# GRUBswitch_CustomHW_RevC.net
KiCad netlist of a schematic drawn in EAGLE
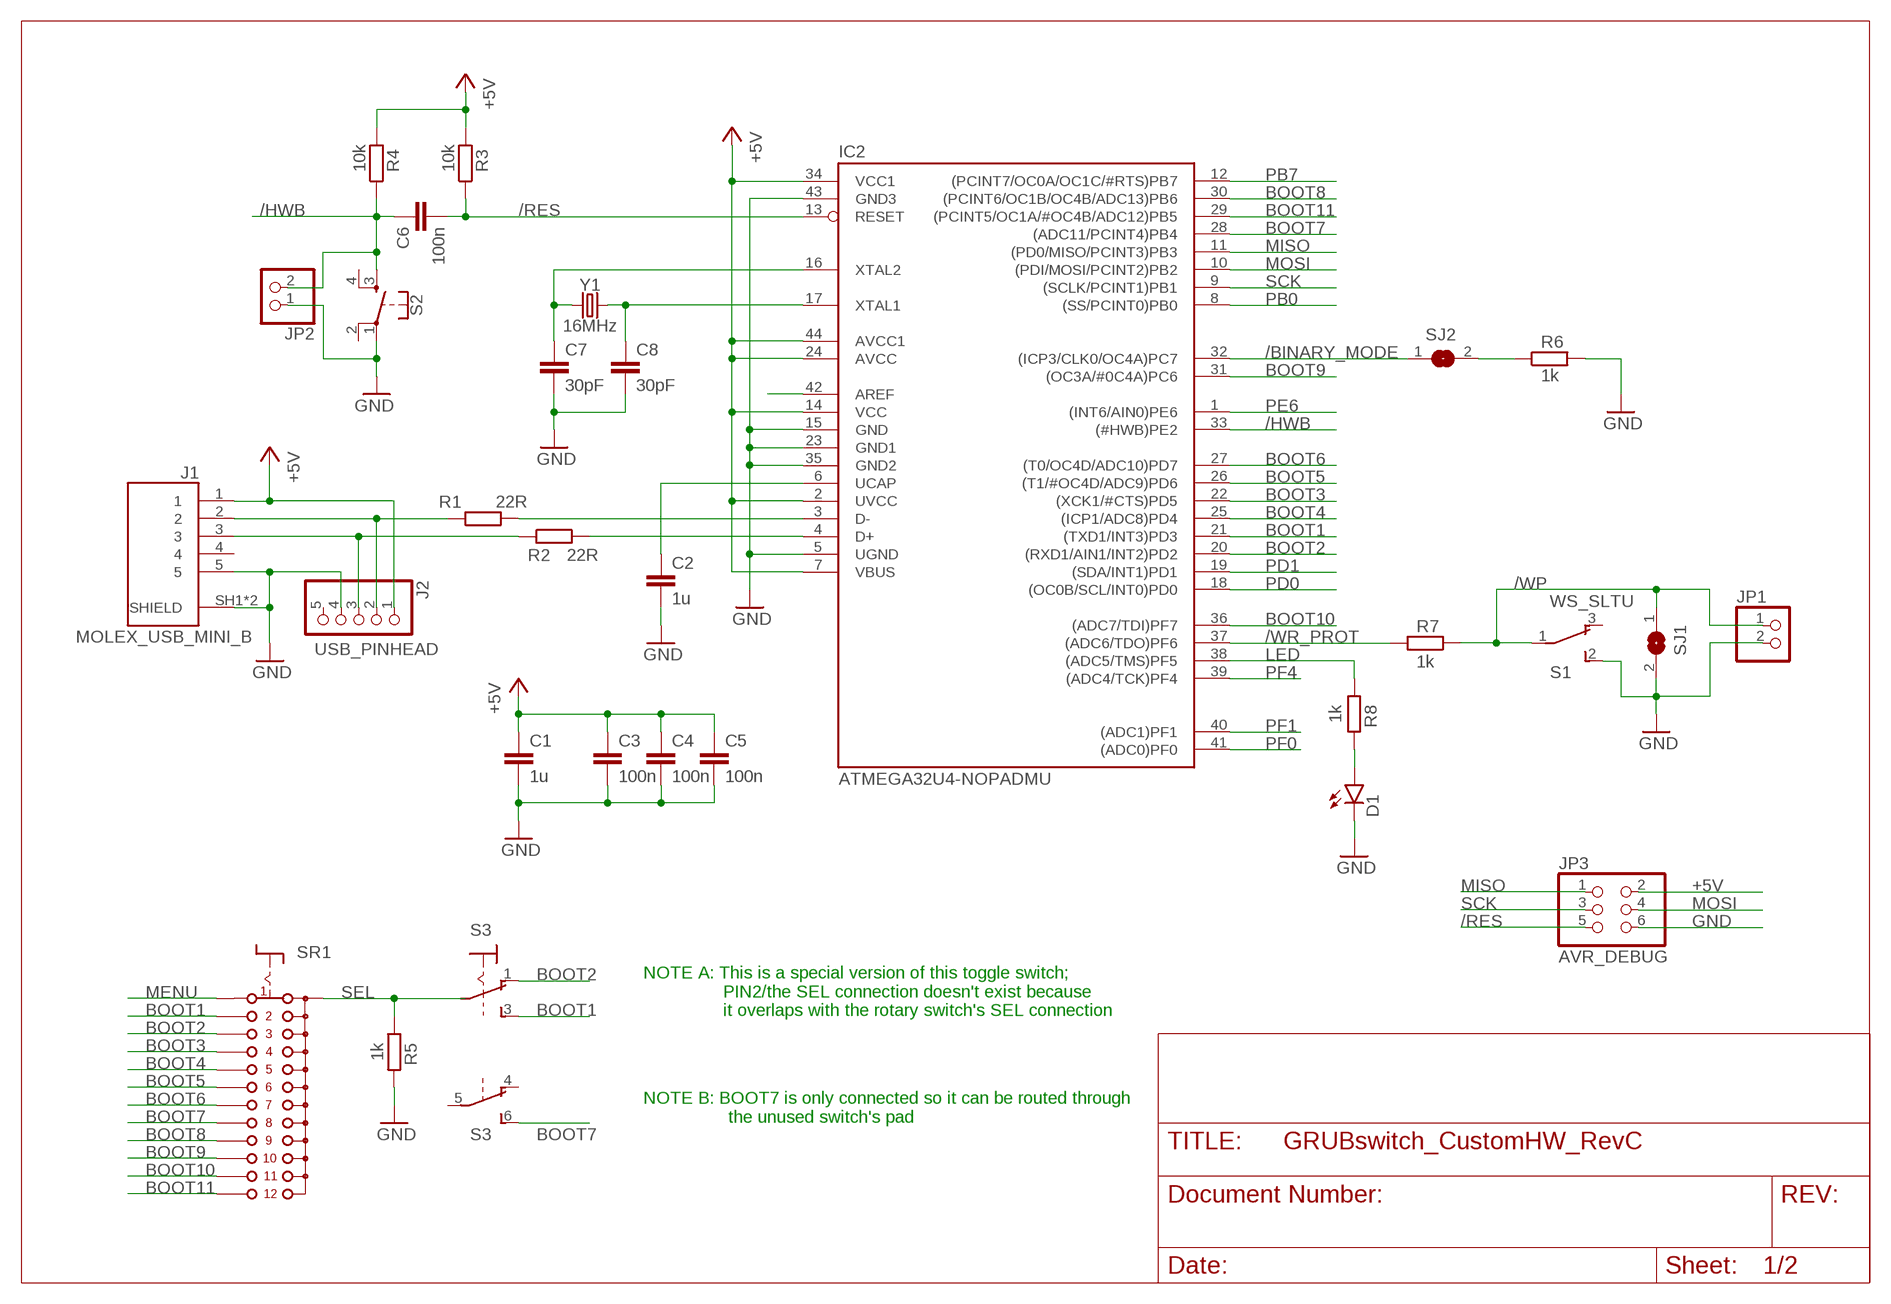
[diagram p0: schematic, sheet 1]
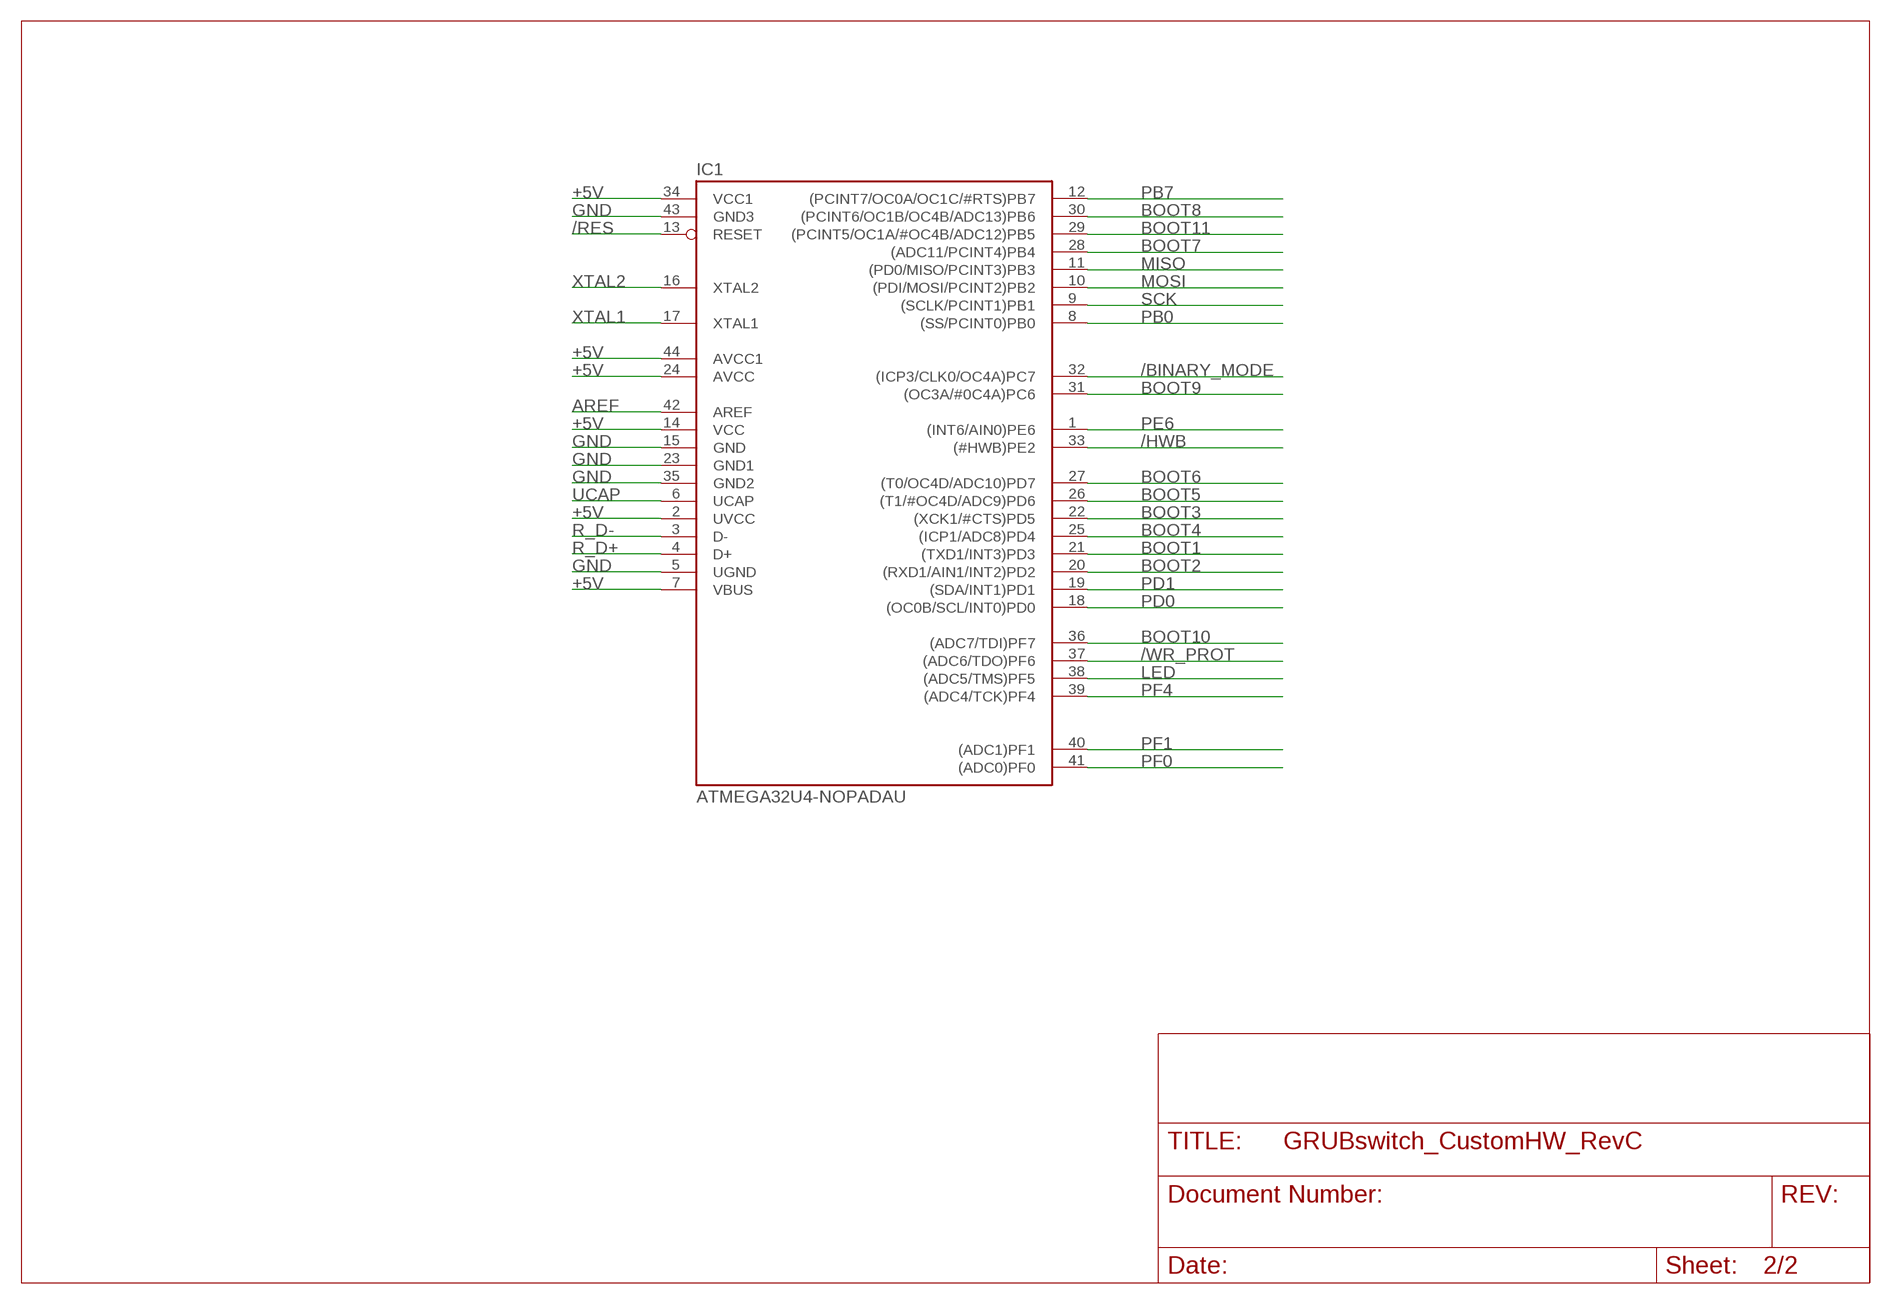
[diagram p1: schematic, sheet 2]

(export (version "E")
  (design (tool "Eeschema 10.0.6"))
  (components
    (comp (ref "C1")
      (value "1u")
      (footprint "eagle-import:C0805")
      (libsource (lib "eagle-import") (part "C-EUC0805"))
    )
    (comp (ref "C2")
      (value "1u")
      (footprint "eagle-import:C0805")
      (libsource (lib "eagle-import") (part "C-EUC0805"))
    )
    (comp (ref "C3")
      (value "100n")
      (footprint "eagle-import:C0805")
      (libsource (lib "eagle-import") (part "C-EUC0805"))
    )
    (comp (ref "C4")
      (value "100n")
      (footprint "eagle-import:C0805")
      (libsource (lib "eagle-import") (part "C-EUC0805"))
    )
    (comp (ref "C5")
      (value "100n")
      (footprint "eagle-import:C0805")
      (libsource (lib "eagle-import") (part "C-EUC0805"))
    )
    (comp (ref "C6")
      (value "100n")
      (footprint "eagle-import:C0805")
      (libsource (lib "eagle-import") (part "C-EUC0805"))
    )
    (comp (ref "C7")
      (value "30pF")
      (footprint "eagle-import:C0805")
      (libsource (lib "eagle-import") (part "C-EUC0805"))
    )
    (comp (ref "C8")
      (value "30pF")
      (footprint "eagle-import:C0805")
      (libsource (lib "eagle-import") (part "C-EUC0805"))
    )
    (comp (ref "D1")
      (value "LEDCHIPLED_0805")
      (footprint "eagle-import:CHIPLED_0805")
      (libsource (lib "eagle-import") (part "LEDCHIPLED_0805"))
    )
    (comp (ref "IC2")
      (value "ATMEGA32U4-NOPADMU")
      (footprint "eagle-import:QFN-44-NOPAD")
      (libsource (lib "eagle-import") (part "ATMEGA32U4-NOPADMU"))
    )
    (comp (ref "J1")
      (value "MOLEX_USB_MINI_B")
      (footprint "eagle-import:MOLEX_502237-0517")
      (libsource (lib "eagle-import") (part "MOLEX_USB_MINI_B"))
    )
    (comp (ref "J2")
      (value "USB_PINHEAD")
      (footprint "eagle-import:1X05")
      (libsource (lib "eagle-import") (part "PINHD-1X5"))
    )
    (comp (ref "JP1")
      (value "PINHD-1X2")
      (footprint "eagle-import:1X02")
      (libsource (lib "eagle-import") (part "PINHD-1X2"))
    )
    (comp (ref "JP2")
      (value "PINHD-1X2")
      (footprint "eagle-import:1X02")
      (libsource (lib "eagle-import") (part "PINHD-1X2"))
    )
    (comp (ref "JP3")
      (value "AVR_DEBUG")
      (footprint "eagle-import:2X03_SMD")
      (libsource (lib "eagle-import") (part "PINHD-2X3SMD"))
    )
    (comp (ref "R1")
      (value "22R")
      (footprint "eagle-import:R0805")
      (libsource (lib "eagle-import") (part "R-EU_R0805"))
    )
    (comp (ref "R2")
      (value "22R")
      (footprint "eagle-import:R0805")
      (libsource (lib "eagle-import") (part "R-EU_R0805"))
    )
    (comp (ref "R3")
      (value "10k")
      (footprint "eagle-import:R0805")
      (libsource (lib "eagle-import") (part "R-EU_R0805"))
    )
    (comp (ref "R4")
      (value "10k")
      (footprint "eagle-import:R0805")
      (libsource (lib "eagle-import") (part "R-EU_R0805"))
    )
    (comp (ref "R5")
      (value "1k")
      (footprint "eagle-import:R0805")
      (libsource (lib "eagle-import") (part "R-EU_R0805"))
    )
    (comp (ref "R6")
      (value "1k")
      (footprint "eagle-import:R0805")
      (libsource (lib "eagle-import") (part "R-EU_R0805"))
    )
    (comp (ref "R7")
      (value "1k")
      (footprint "eagle-import:R0805")
      (libsource (lib "eagle-import") (part "R-EU_R0805"))
    )
    (comp (ref "R8")
      (value "1k")
      (footprint "eagle-import:R0805")
      (libsource (lib "eagle-import") (part "R-EU_R0805"))
    )
    (comp (ref "S1")
      (value "WS_SLTU")
      (footprint "eagle-import:WS_SLTU")
      (libsource (lib "eagle-import") (part "WS_SLTU"))
    )
    (comp (ref "S2")
      (value "MOMENTARY-SWITCH-SPST-2-SMD-4.5MM")
      (footprint "eagle-import:TACTILE_SWITCH_SMD_4.5MM")
      (libsource (lib "eagle-import") (part "MOMENTARY-SWITCH-SPST-2-SMD-4.5MM"))
    )
    (comp (ref "S3")
      (value "M9040P2")
      (footprint "eagle-import:M9040P2")
      (libsource (lib "eagle-import") (part "M9040P2"))
    )
    (comp (ref "SJ1") (value "SJ") (footprint "eagle-import:SJ") (libsource (lib "eagle-import") (part "SJ")))
    (comp (ref "SJ2") (value "SJ") (footprint "eagle-import:SJ") (libsource (lib "eagle-import") (part "SJ")))
    (comp (ref "SR1")
      (value "CK101X12+")
      (footprint "eagle-import:CK101X12+")
      (libsource (lib "eagle-import") (part "CK101X12+"))
    )
    (comp (ref "Y1")
      (value "16MHz")
      (footprint "eagle-import:CRYSTAL-SMD-5X3.2-2PAD")
      (libsource (lib "eagle-import") (part "CRYSTALSMD-5X3.2-2PAD"))
    )
    (comp (ref "IC1")
      (value "ATMEGA32U4-NOPADAU")
      (footprint "eagle-import:TQFP44")
      (libsource (lib "eagle-import") (part "ATMEGA32U4-NOPADAU"))
    )
  )
  (nets
    (net (code "1") (name "+5V") (class "Default")
      (node (ref "C1") (pin "1") (pinfunction "1_1") (pintype "passive"))
      (node (ref "C3") (pin "1") (pinfunction "1_1") (pintype "passive"))
      (node (ref "C4") (pin "1") (pinfunction "1_1") (pintype "passive"))
      (node (ref "C5") (pin "1") (pinfunction "1_1") (pintype "passive"))
      (node (ref "IC1") (pin "14") (pinfunction "VCC_14") (pintype "power_in"))
      (node (ref "IC1") (pin "2") (pinfunction "UVCC_2") (pintype "power_in"))
      (node (ref "IC1") (pin "24") (pinfunction "AVCC_24") (pintype "power_in"))
      (node (ref "IC1") (pin "34") (pinfunction "VCC1_34") (pintype "power_in"))
      (node (ref "IC1") (pin "44") (pinfunction "AVCC1_44") (pintype "power_in"))
      (node (ref "IC1") (pin "7") (pinfunction "VBUS_7") (pintype "input"))
      (node (ref "IC2") (pin "14") (pinfunction "VCC_14") (pintype "power_in"))
      (node (ref "IC2") (pin "2") (pinfunction "UVCC_2") (pintype "power_in"))
      (node (ref "IC2") (pin "24") (pinfunction "AVCC_24") (pintype "power_in"))
      (node (ref "IC2") (pin "34") (pinfunction "VCC1_34") (pintype "power_in"))
      (node (ref "IC2") (pin "44") (pinfunction "AVCC1_44") (pintype "power_in"))
      (node (ref "IC2") (pin "7") (pinfunction "VBUS_7") (pintype "input"))
      (node (ref "J1") (pin "1") (pinfunction "1_1") (pintype "passive"))
      (node (ref "J2") (pin "1") (pinfunction "1_1") (pintype "passive"))
      (node (ref "JP3") (pin "2") (pinfunction "2_2") (pintype "passive"))
      (node (ref "R3") (pin "2") (pinfunction "2_2") (pintype "passive"))
      (node (ref "R4") (pin "2") (pinfunction "2_2") (pintype "passive"))
    )
    (net (code "2") (name "AREF") (class "Default")
      (node (ref "IC1") (pin "42") (pinfunction "AREF_42") (pintype "power_in"))
      (node (ref "IC2") (pin "42") (pinfunction "AREF_42") (pintype "power_in"))
    )
    (net (code "3") (name "BOOT1") (class "Default")
      (node (ref "IC1") (pin "21") (pinfunction "(TXD1/INT3)PD3_21") (pintype "bidirectional"))
      (node (ref "IC2") (pin "21") (pinfunction "(TXD1/INT3)PD3_21") (pintype "bidirectional"))
      (node (ref "S3") (pin "3") (pinfunction "S_3") (pintype "passive"))
      (node (ref "SR1") (pin "2") (pinfunction "2_2") (pintype "passive"))
    )
    (net (code "4") (name "BOOT2") (class "Default")
      (node (ref "IC1") (pin "20") (pinfunction "(RXD1/AIN1/INT2)PD2_20") (pintype "bidirectional"))
      (node (ref "IC2") (pin "20") (pinfunction "(RXD1/AIN1/INT2)PD2_20") (pintype "bidirectional"))
      (node (ref "S3") (pin "1") (pinfunction "O_1") (pintype "passive"))
      (node (ref "SR1") (pin "3") (pinfunction "3_3") (pintype "passive"))
    )
    (net (code "5") (name "BOOT3") (class "Default")
      (node (ref "IC1") (pin "22") (pinfunction "(XCK1/#CTS)PD5_22") (pintype "bidirectional"))
      (node (ref "IC2") (pin "22") (pinfunction "(XCK1/#CTS)PD5_22") (pintype "bidirectional"))
      (node (ref "SR1") (pin "4") (pinfunction "4_4") (pintype "passive"))
    )
    (net (code "6") (name "BOOT4") (class "Default")
      (node (ref "IC1") (pin "25") (pinfunction "(ICP1/ADC8)PD4_25") (pintype "bidirectional"))
      (node (ref "IC2") (pin "25") (pinfunction "(ICP1/ADC8)PD4_25") (pintype "bidirectional"))
      (node (ref "SR1") (pin "5") (pinfunction "5_5") (pintype "passive"))
    )
    (net (code "7") (name "BOOT5") (class "Default")
      (node (ref "IC1") (pin "26") (pinfunction "(T1/#OC4D/ADC9)PD6_26") (pintype "bidirectional"))
      (node (ref "IC2") (pin "26") (pinfunction "(T1/#OC4D/ADC9)PD6_26") (pintype "bidirectional"))
      (node (ref "SR1") (pin "6") (pinfunction "6_6") (pintype "passive"))
    )
    (net (code "8") (name "BOOT6") (class "Default")
      (node (ref "IC1") (pin "27") (pinfunction "(T0/OC4D/ADC10)PD7_27") (pintype "bidirectional"))
      (node (ref "IC2") (pin "27") (pinfunction "(T0/OC4D/ADC10)PD7_27") (pintype "bidirectional"))
      (node (ref "SR1") (pin "7") (pinfunction "7_7") (pintype "passive"))
    )
    (net (code "9") (name "BOOT7") (class "Default")
      (node (ref "IC1") (pin "28") (pinfunction "(ADC11/PCINT4)PB4_28") (pintype "bidirectional"))
      (node (ref "IC2") (pin "28") (pinfunction "(ADC11/PCINT4)PB4_28") (pintype "bidirectional"))
      (node (ref "S3") (pin "6") (pinfunction "S_6") (pintype "passive"))
      (node (ref "SR1") (pin "8") (pinfunction "8_8") (pintype "passive"))
    )
    (net (code "10") (name "BOOT8") (class "Default")
      (node (ref "IC1") (pin "30") (pinfunction "(PCINT6/OC1B/OC4B/ADC13)PB6_30") (pintype "bidirectional"))
      (node (ref "IC2") (pin "30") (pinfunction "(PCINT6/OC1B/OC4B/ADC13)PB6_30") (pintype "bidirectional"))
      (node (ref "SR1") (pin "9") (pinfunction "9_9") (pintype "passive"))
    )
    (net (code "11") (name "BOOT9") (class "Default")
      (node (ref "IC1") (pin "31") (pinfunction "(OC3A/#0C4A)PC6_31") (pintype "bidirectional"))
      (node (ref "IC2") (pin "31") (pinfunction "(OC3A/#0C4A)PC6_31") (pintype "bidirectional"))
      (node (ref "SR1") (pin "10") (pinfunction "10_10") (pintype "passive"))
    )
    (net (code "12") (name "BOOT10") (class "Default")
      (node (ref "IC1") (pin "36") (pinfunction "(ADC7/TDI)PF7_36") (pintype "bidirectional"))
      (node (ref "IC2") (pin "36") (pinfunction "(ADC7/TDI)PF7_36") (pintype "bidirectional"))
      (node (ref "SR1") (pin "11") (pinfunction "11_11") (pintype "passive"))
    )
    (net (code "13") (name "BOOT11") (class "Default")
      (node (ref "IC1") (pin "29") (pinfunction "(PCINT5/OC1A/#OC4B/ADC12)PB5_29") (pintype "bidirectional"))
      (node (ref "IC2") (pin "29") (pinfunction "(PCINT5/OC1A/#OC4B/ADC12)PB5_29") (pintype "bidirectional"))
      (node (ref "SR1") (pin "12") (pinfunction "12_12") (pintype "passive"))
    )
    (net (code "14") (name "GND") (class "Default")
      (node (ref "C1") (pin "2") (pinfunction "2_2") (pintype "passive"))
      (node (ref "C2") (pin "2") (pinfunction "2_2") (pintype "passive"))
      (node (ref "C3") (pin "2") (pinfunction "2_2") (pintype "passive"))
      (node (ref "C4") (pin "2") (pinfunction "2_2") (pintype "passive"))
      (node (ref "C5") (pin "2") (pinfunction "2_2") (pintype "passive"))
      (node (ref "C7") (pin "2") (pinfunction "2_2") (pintype "passive"))
      (node (ref "C8") (pin "2") (pinfunction "2_2") (pintype "passive"))
      (node (ref "D1") (pin "C") (pinfunction "C_C") (pintype "passive"))
      (node (ref "IC1") (pin "15") (pinfunction "GND_15") (pintype "power_in"))
      (node (ref "IC1") (pin "23") (pinfunction "GND1_23") (pintype "power_in"))
      (node (ref "IC1") (pin "35") (pinfunction "GND2_35") (pintype "power_in"))
      (node (ref "IC1") (pin "43") (pinfunction "GND3_43") (pintype "power_in"))
      (node (ref "IC1") (pin "5") (pinfunction "UGND_5") (pintype "power_in"))
      (node (ref "IC2") (pin "15") (pinfunction "GND_15") (pintype "power_in"))
      (node (ref "IC2") (pin "23") (pinfunction "GND1_23") (pintype "power_in"))
      (node (ref "IC2") (pin "35") (pinfunction "GND2_35") (pintype "power_in"))
      (node (ref "IC2") (pin "43") (pinfunction "GND3_43") (pintype "power_in"))
      (node (ref "IC2") (pin "5") (pinfunction "UGND_5") (pintype "power_in"))
      (node (ref "J1") (pin "5") (pinfunction "5_5") (pintype "passive"))
      (node (ref "J1") (pin "SH1") (pinfunction "SHIELD_SH1") (pintype "passive"))
      (node (ref "J1") (pin "SH2") (pinfunction "SHIELD_SH2") (pintype "passive"))
      (node (ref "J2") (pin "4") (pinfunction "4_4") (pintype "passive"))
      (node (ref "JP1") (pin "2") (pinfunction "2_2") (pintype "passive"))
      (node (ref "JP2") (pin "1") (pinfunction "1_1") (pintype "passive"))
      (node (ref "JP3") (pin "6") (pinfunction "6_6") (pintype "passive"))
      (node (ref "R5") (pin "2") (pinfunction "2_2") (pintype "passive"))
      (node (ref "R6") (pin "2") (pinfunction "2_2") (pintype "passive"))
      (node (ref "S1") (pin "2") (pinfunction "S_2") (pintype "passive"))
      (node (ref "S2") (pin "1") (pinfunction "1_1") (pintype "passive"))
      (node (ref "SJ1") (pin "2") (pinfunction "2_2") (pintype "passive"))
    )
    (net (code "15") (name "LED") (class "Default")
      (node (ref "IC1") (pin "38") (pinfunction "(ADC5/TMS)PF5_38") (pintype "bidirectional"))
      (node (ref "IC2") (pin "38") (pinfunction "(ADC5/TMS)PF5_38") (pintype "bidirectional"))
      (node (ref "R8") (pin "2") (pinfunction "2_2") (pintype "passive"))
    )
    (net (code "16") (name "MENU") (class "Default")
      (node (ref "SR1") (pin "1") (pinfunction "1_1") (pintype "passive"))
    )
    (net (code "17") (name "MISO") (class "Default")
      (node (ref "IC1") (pin "11") (pinfunction "(PD0/MISO/PCINT3)PB3_11") (pintype "bidirectional"))
      (node (ref "IC2") (pin "11") (pinfunction "(PD0/MISO/PCINT3)PB3_11") (pintype "bidirectional"))
      (node (ref "JP3") (pin "1") (pinfunction "1_1") (pintype "passive"))
    )
    (net (code "18") (name "MOSI") (class "Default")
      (node (ref "IC1") (pin "10") (pinfunction "(PDI/MOSI/PCINT2)PB2_10") (pintype "bidirectional"))
      (node (ref "IC2") (pin "10") (pinfunction "(PDI/MOSI/PCINT2)PB2_10") (pintype "bidirectional"))
      (node (ref "JP3") (pin "4") (pinfunction "4_4") (pintype "passive"))
    )
    (net (code "19") (name "Net-(D1-PadA)") (class "Default")
      (node (ref "D1") (pin "A") (pinfunction "A_A") (pintype "passive"))
      (node (ref "R8") (pin "1") (pinfunction "1_1") (pintype "passive"))
    )
    (net (code "20") (name "Net-(J1-Pad2)") (class "Default")
      (node (ref "J1") (pin "2") (pinfunction "2_2") (pintype "passive"))
      (node (ref "J2") (pin "2") (pinfunction "2_2") (pintype "passive"))
      (node (ref "R1") (pin "1") (pinfunction "1_1") (pintype "passive"))
    )
    (net (code "21") (name "Net-(J1-Pad3)") (class "Default")
      (node (ref "J1") (pin "3") (pinfunction "3_3") (pintype "passive"))
      (node (ref "J2") (pin "3") (pinfunction "3_3") (pintype "passive"))
      (node (ref "R2") (pin "1") (pinfunction "1_1") (pintype "passive"))
    )
    (net (code "22") (name "Net-(R6-Pad1)") (class "Default")
      (node (ref "R6") (pin "1") (pinfunction "1_1") (pintype "passive"))
      (node (ref "SJ2") (pin "2") (pinfunction "2_2") (pintype "passive"))
    )
    (net (code "23") (name "PB0") (class "Default")
      (node (ref "IC1") (pin "8") (pinfunction "(SS/PCINT0)PB0_8") (pintype "bidirectional"))
      (node (ref "IC2") (pin "8") (pinfunction "(SS/PCINT0)PB0_8") (pintype "bidirectional"))
    )
    (net (code "24") (name "PB7") (class "Default")
      (node (ref "IC1") (pin "12") (pinfunction "(PCINT7/OC0A/OC1C/#RTS)PB7_12") (pintype "bidirectional"))
      (node (ref "IC2") (pin "12") (pinfunction "(PCINT7/OC0A/OC1C/#RTS)PB7_12") (pintype "bidirectional"))
    )
    (net (code "25") (name "PD0") (class "Default")
      (node (ref "IC1") (pin "18") (pinfunction "(OC0B/SCL/INT0)PD0_18") (pintype "bidirectional"))
      (node (ref "IC2") (pin "18") (pinfunction "(OC0B/SCL/INT0)PD0_18") (pintype "bidirectional"))
    )
    (net (code "26") (name "PD1") (class "Default")
      (node (ref "IC1") (pin "19") (pinfunction "(SDA/INT1)PD1_19") (pintype "bidirectional"))
      (node (ref "IC2") (pin "19") (pinfunction "(SDA/INT1)PD1_19") (pintype "bidirectional"))
    )
    (net (code "27") (name "PE6") (class "Default")
      (node (ref "IC1") (pin "1") (pinfunction "(INT6/AIN0)PE6_1") (pintype "bidirectional"))
      (node (ref "IC2") (pin "1") (pinfunction "(INT6/AIN0)PE6_1") (pintype "bidirectional"))
    )
    (net (code "28") (name "PF0") (class "Default")
      (node (ref "IC1") (pin "41") (pinfunction "(ADC0)PF0_41") (pintype "bidirectional"))
      (node (ref "IC2") (pin "41") (pinfunction "(ADC0)PF0_41") (pintype "bidirectional"))
    )
    (net (code "29") (name "PF1") (class "Default")
      (node (ref "IC1") (pin "40") (pinfunction "(ADC1)PF1_40") (pintype "bidirectional"))
      (node (ref "IC2") (pin "40") (pinfunction "(ADC1)PF1_40") (pintype "bidirectional"))
    )
    (net (code "30") (name "PF4") (class "Default")
      (node (ref "IC1") (pin "39") (pinfunction "(ADC4/TCK)PF4_39") (pintype "bidirectional"))
      (node (ref "IC2") (pin "39") (pinfunction "(ADC4/TCK)PF4_39") (pintype "bidirectional"))
    )
    (net (code "31") (name "R_D+") (class "Default")
      (node (ref "IC1") (pin "4") (pinfunction "D+_4") (pintype "bidirectional"))
      (node (ref "IC2") (pin "4") (pinfunction "D+_4") (pintype "bidirectional"))
      (node (ref "R2") (pin "2") (pinfunction "2_2") (pintype "passive"))
    )
    (net (code "32") (name "R_D-") (class "Default")
      (node (ref "IC1") (pin "3") (pinfunction "D-_3") (pintype "bidirectional"))
      (node (ref "IC2") (pin "3") (pinfunction "D-_3") (pintype "bidirectional"))
      (node (ref "R1") (pin "2") (pinfunction "2_2") (pintype "passive"))
    )
    (net (code "33") (name "SCK") (class "Default")
      (node (ref "IC1") (pin "9") (pinfunction "(SCLK/PCINT1)PB1_9") (pintype "bidirectional"))
      (node (ref "IC2") (pin "9") (pinfunction "(SCLK/PCINT1)PB1_9") (pintype "bidirectional"))
      (node (ref "JP3") (pin "3") (pinfunction "3_3") (pintype "passive"))
    )
    (net (code "34") (name "SEL") (class "Default")
      (node (ref "R5") (pin "1") (pinfunction "1_1") (pintype "passive"))
      (node (ref "SR1") (pin "A") (pinfunction "A_A") (pintype "passive"))
    )
    (net (code "35") (name "UCAP") (class "Default")
      (node (ref "C2") (pin "1") (pinfunction "1_1") (pintype "passive"))
      (node (ref "IC1") (pin "6") (pinfunction "UCAP_6") (pintype "passive"))
      (node (ref "IC2") (pin "6") (pinfunction "UCAP_6") (pintype "passive"))
    )
    (net (code "36") (name "XTAL1") (class "Default")
      (node (ref "C8") (pin "1") (pinfunction "1_1") (pintype "passive"))
      (node (ref "IC1") (pin "17") (pinfunction "XTAL1_17") (pintype "bidirectional"))
      (node (ref "IC2") (pin "17") (pinfunction "XTAL1_17") (pintype "bidirectional"))
      (node (ref "Y1") (pin "P$2") (pinfunction "2_P$2") (pintype "passive"))
    )
    (net (code "37") (name "XTAL2") (class "Default")
      (node (ref "C7") (pin "1") (pinfunction "1_1") (pintype "passive"))
      (node (ref "IC1") (pin "16") (pinfunction "XTAL2_16") (pintype "bidirectional"))
      (node (ref "IC2") (pin "16") (pinfunction "XTAL2_16") (pintype "bidirectional"))
      (node (ref "Y1") (pin "P$1") (pinfunction "1_P$1") (pintype "passive"))
    )
    (net (code "38") (name "unconnected-(J1-Pad4)") (class "Default")
      (node (ref "J1") (pin "4") (pinfunction "4_4") (pintype "passive"))
    )
    (net (code "39") (name "unconnected-(J2-Pad5)") (class "Default")
      (node (ref "J2") (pin "5") (pinfunction "5_5") (pintype "passive"))
    )
    (net (code "40") (name "unconnected-(S1-O-Pad3)") (class "Default")
      (node (ref "S1") (pin "3") (pinfunction "O_3") (pintype "passive"))
    )
    (net (code "41") (name "unconnected-(S2-Pad2)") (class "Default")
      (node (ref "S2") (pin "2") (pinfunction "2_2") (pintype "passive"))
    )
    (net (code "42") (name "unconnected-(S2-Pad4)") (class "Default")
      (node (ref "S2") (pin "4") (pinfunction "4_4") (pintype "passive"))
    )
    (net (code "43") (name "unconnected-(S3B-O-Pad4)") (class "Default")
      (node (ref "S3") (pin "4") (pinfunction "O_4") (pintype "passive"))
    )
    (net (code "44") (name "unconnected-(S3B-P-Pad5)") (class "Default")
      (node (ref "S3") (pin "5") (pinfunction "P_5") (pintype "passive"))
    )
    (net (code "45") (name "{slash}BINARY_MODE") (class "Default")
      (node (ref "IC1") (pin "32") (pinfunction "(ICP3/CLK0/OC4A)PC7_32") (pintype "bidirectional"))
      (node (ref "IC2") (pin "32") (pinfunction "(ICP3/CLK0/OC4A)PC7_32") (pintype "bidirectional"))
      (node (ref "SJ2") (pin "1") (pinfunction "1_1") (pintype "passive"))
    )
    (net (code "46") (name "{slash}HWB") (class "Default")
      (node (ref "C6") (pin "1") (pinfunction "1_1") (pintype "passive"))
      (node (ref "IC1") (pin "33") (pinfunction "(#HWB)PE2_33") (pintype "bidirectional"))
      (node (ref "IC2") (pin "33") (pinfunction "(#HWB)PE2_33") (pintype "bidirectional"))
      (node (ref "JP2") (pin "2") (pinfunction "2_2") (pintype "passive"))
      (node (ref "R4") (pin "1") (pinfunction "1_1") (pintype "passive"))
      (node (ref "S2") (pin "3") (pinfunction "3_3") (pintype "passive"))
    )
    (net (code "47") (name "{slash}RES") (class "Default")
      (node (ref "C6") (pin "2") (pinfunction "2_2") (pintype "passive"))
      (node (ref "IC1") (pin "13") (pinfunction "RESET_13") (pintype "input"))
      (node (ref "IC2") (pin "13") (pinfunction "RESET_13") (pintype "input"))
      (node (ref "JP3") (pin "5") (pinfunction "5_5") (pintype "passive"))
      (node (ref "R3") (pin "1") (pinfunction "1_1") (pintype "passive"))
    )
    (net (code "48") (name "{slash}WP") (class "Default")
      (node (ref "JP1") (pin "1") (pinfunction "1_1") (pintype "passive"))
      (node (ref "R7") (pin "1") (pinfunction "1_1") (pintype "passive"))
      (node (ref "S1") (pin "1") (pinfunction "P_1") (pintype "passive"))
      (node (ref "SJ1") (pin "1") (pinfunction "1_1") (pintype "passive"))
    )
    (net (code "49") (name "{slash}WR_PROT") (class "Default")
      (node (ref "IC1") (pin "37") (pinfunction "(ADC6/TDO)PF6_37") (pintype "bidirectional"))
      (node (ref "IC2") (pin "37") (pinfunction "(ADC6/TDO)PF6_37") (pintype "bidirectional"))
      (node (ref "R7") (pin "2") (pinfunction "2_2") (pintype "passive"))
    )
  )
)
